# Memory_Add_Register.net
KiCad netlist of a schematic drawn in Altium Designer
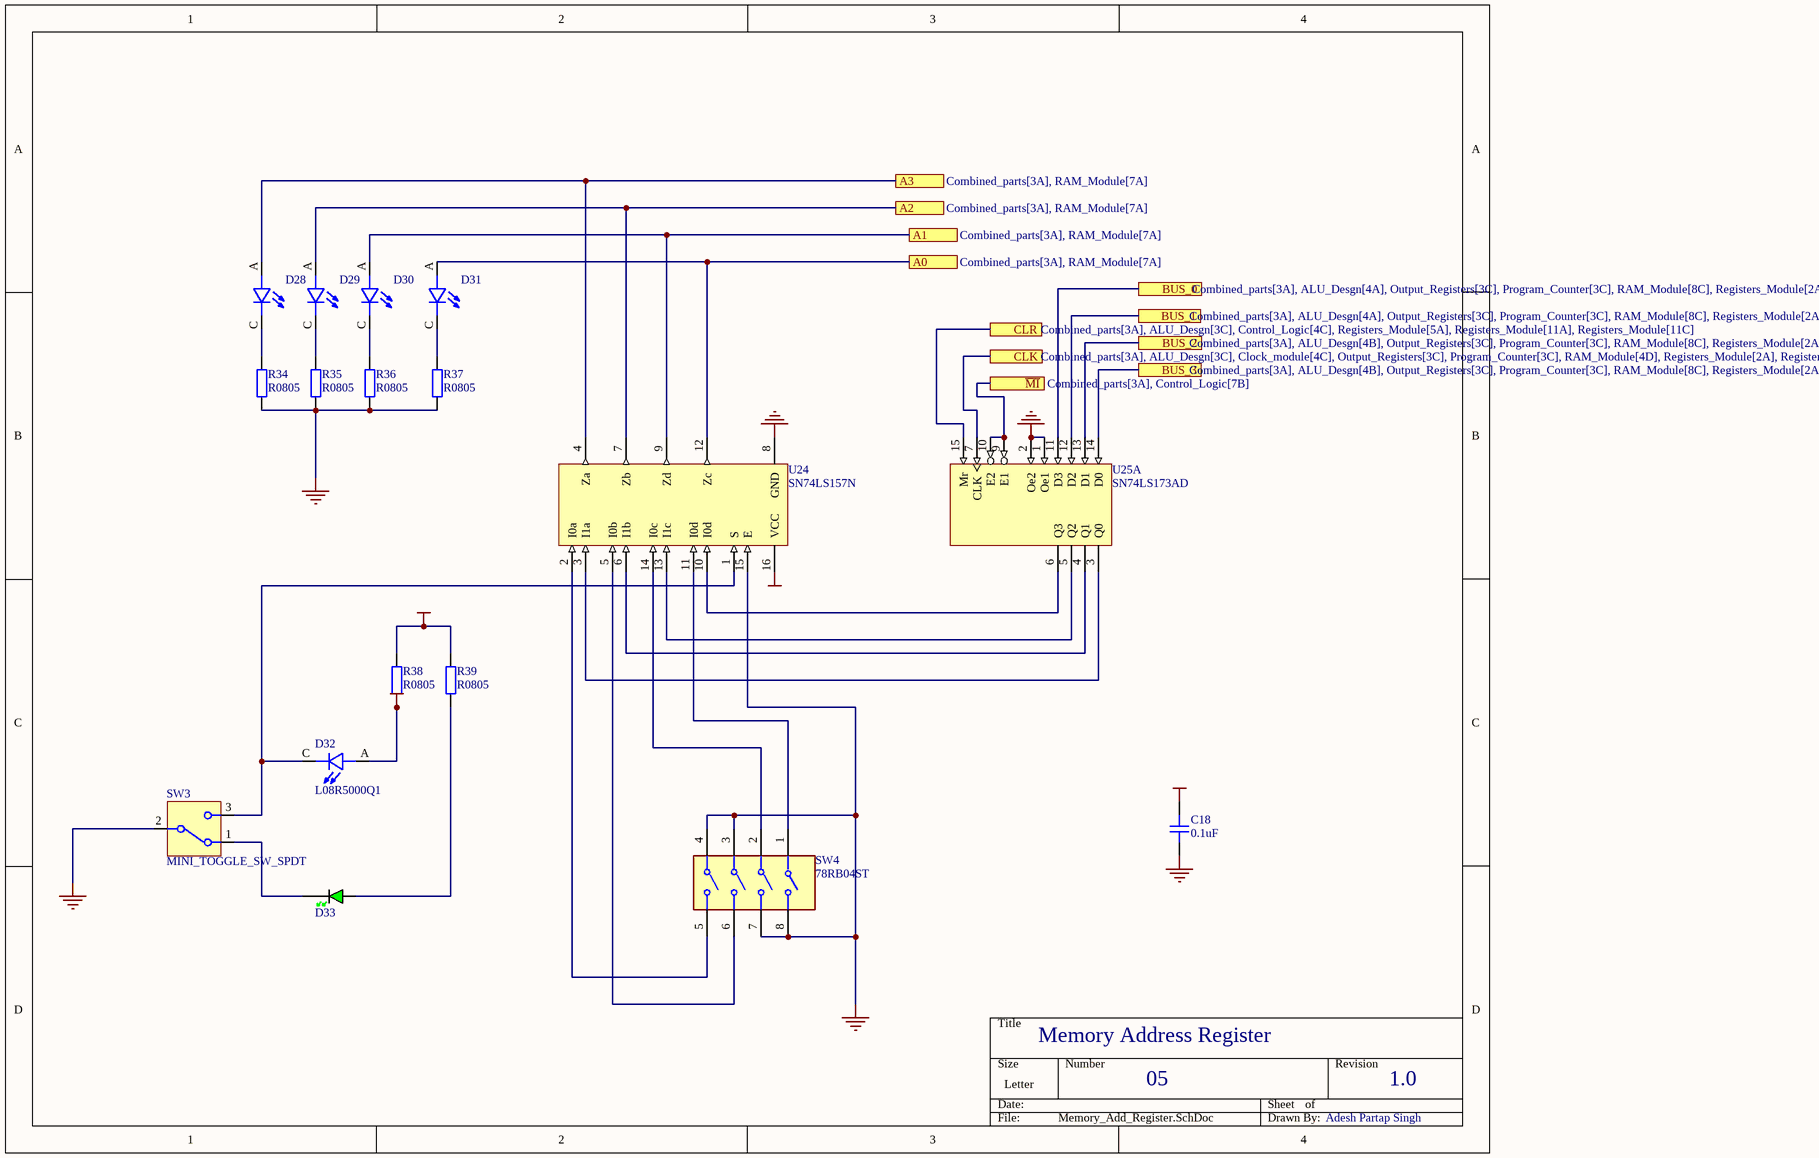
[diagram p0: Memory_Add_Register.SchDoc]

(export (version "E")
  (design (tool "Eeschema 10.0.6"))
  (components
    (comp (ref "C18")
      (value "0.1uF")
      (footprint "CAP_0805")
      (description "Capacitor SMD 0805")
      (libsource (lib "Schematic-Lib-PhilsLab") (part "CAP_0805"))
    )
    (comp (ref "D28")
      (value "L08R5000Q1")
      (footprint "LEDRD254W57D500H1070")
      (fields (field (name "MF") "LED Technology"))
      (libsource (lib "8BIT_COMP_LIB") (part "L08R5000Q1"))
    )
    (comp (ref "D29")
      (value "L08R5000Q1")
      (footprint "LEDRD254W57D500H1070")
      (fields (field (name "MF") "LED Technology"))
      (libsource (lib "8BIT_COMP_LIB") (part "L08R5000Q1"))
    )
    (comp (ref "D30")
      (value "L08R5000Q1")
      (footprint "LEDRD254W57D500H1070")
      (fields (field (name "MF") "LED Technology"))
      (libsource (lib "8BIT_COMP_LIB") (part "L08R5000Q1"))
    )
    (comp (ref "D31")
      (value "L08R5000Q1")
      (footprint "LEDRD254W57D500H1070")
      (fields (field (name "MF") "LED Technology"))
      (libsource (lib "8BIT_COMP_LIB") (part "L08R5000Q1"))
    )
    (comp (ref "D32")
      (value "L08R5000Q1")
      (footprint "LEDRD254W57D500H1070")
      (fields (field (name "MF") "LED Technology"))
      (libsource (lib "8BIT_COMP_LIB") (part "L08R5000Q1"))
    )
    (comp (ref "D33")
      (value "GREEN")
      (footprint "LED_0805_GREEN")
      (description "LED 0805 GREEN SMD")
      (libsource (lib "Schematic-Lib-PhilsLab") (part "LED_0805_GREEN"))
    )
    (comp (ref "R34")
      (value "R0805")
      (footprint "RES_0805")
      (description "Resistor SMD 0805")
      (libsource (lib "Schematic-Lib-PhilsLab") (part "RES_0805"))
    )
    (comp (ref "R35")
      (value "R0805")
      (footprint "RES_0805")
      (description "Resistor SMD 0805")
      (libsource (lib "Schematic-Lib-PhilsLab") (part "RES_0805"))
    )
    (comp (ref "R36")
      (value "R0805")
      (footprint "RES_0805")
      (description "Resistor SMD 0805")
      (libsource (lib "Schematic-Lib-PhilsLab") (part "RES_0805"))
    )
    (comp (ref "R37")
      (value "R0805")
      (footprint "RES_0805")
      (description "Resistor SMD 0805")
      (libsource (lib "Schematic-Lib-PhilsLab") (part "RES_0805"))
    )
    (comp (ref "R38")
      (value "R0805")
      (footprint "RES_0805")
      (description "Resistor SMD 0805")
      (libsource (lib "Schematic-Lib-PhilsLab") (part "RES_0805"))
    )
    (comp (ref "R39")
      (value "R0805")
      (footprint "RES_0805")
      (description "Resistor SMD 0805")
      (libsource (lib "Schematic-Lib-PhilsLab") (part "RES_0805"))
    )
    (comp (ref "SW3")
      (value "MINI_TOGGLE_SW_SPDT")
      (footprint "MINI_TOGGLE_SW_SPDT")
      (description "Mini Toggle Switch SPDT THT")
      (libsource (lib "Schematic-Lib-PhilsLab") (part "MINI_TOGGLE_SW_SPDT"))
    )
    (comp (ref "SW4")
      (value "78RB04ST")
      (footprint "FP-78RB04ST-MFG")
      (description "SWITCH SLIDE DIP SPST 150MA 30V")
      (libsource (lib "8BIT_COMP_LIB") (part "CMP-31942-000006-1"))
    )
    (comp (ref "U24")
      (value "SN74LS157N")
      (footprint "N0016A")
      (description "Quadruple 2-Line To 1-Line Data Selectors/Multiplexers, N0016A, TUBE")
      (fields
        (field (name "MANUFACTURER") "Texas Instruments")
        (field (name "GENERIC PART NUMBER") "SN74LS157")
      )
      (libsource (lib "8BIT_COMP_LIB") (part "CMP-1633-00683-2"))
    )
    (comp (ref "U25")
      (value "SN74LS173AD")
      (footprint "D0016A_N")
      (description "4-Bit D-type Registers with 3-State Outputs, D0016A, TUBE")
      (fields
        (field (name "GENERIC PART NUMBER") "SN74LS173A")
        (field (name "MANUFACTURER") "Texas Instruments")
      )
      (libsource (lib "8BIT_COMP_LIB") (part "CMP-1616-00008-3"))
    )
  )
  (nets
    (net (code "1") (name "/A0") (class "Default")
      (node (ref "D31") (pin "A") (pinfunction "A_A") (pintype "passive"))
      (node (ref "U24") (pin "12") (pinfunction "Zc_12") (pintype "output"))
    )
    (net (code "2") (name "/A1") (class "Default")
      (node (ref "D30") (pin "A") (pinfunction "A_A") (pintype "passive"))
      (node (ref "U24") (pin "9") (pinfunction "Zd_9") (pintype "output"))
    )
    (net (code "3") (name "/A2") (class "Default")
      (node (ref "D29") (pin "A") (pinfunction "A_A") (pintype "passive"))
      (node (ref "U24") (pin "7") (pinfunction "Zb_7") (pintype "output"))
    )
    (net (code "4") (name "/A3") (class "Default")
      (node (ref "D28") (pin "A") (pinfunction "A_A") (pintype "passive"))
      (node (ref "U24") (pin "4") (pinfunction "Za_4") (pintype "output"))
    )
    (net (code "5") (name "/BUS_0") (class "Default")
      (node (ref "U25") (pin "11") (pinfunction "D3_11") (pintype "input"))
    )
    (net (code "6") (name "/BUS_1") (class "Default")
      (node (ref "U25") (pin "12") (pinfunction "D2_12") (pintype "input"))
    )
    (net (code "7") (name "/BUS_2") (class "Default")
      (node (ref "U25") (pin "13") (pinfunction "D1_13") (pintype "input"))
    )
    (net (code "8") (name "/BUS_3") (class "Default")
      (node (ref "U25") (pin "14") (pinfunction "D0_14") (pintype "input"))
    )
    (net (code "9") (name "/CLK") (class "Default")
      (node (ref "U25") (pin "7") (pinfunction "CLK_7") (pintype "input"))
    )
    (net (code "10") (name "/CLR") (class "Default")
      (node (ref "U25") (pin "15") (pinfunction "Mr_15") (pintype "input"))
    )
    (net (code "11") (name "/~{MI}") (class "Default")
      (node (ref "U25") (pin "10") (pinfunction "E2_10") (pintype "input"))
      (node (ref "U25") (pin "9") (pinfunction "E1_9") (pintype "input"))
    )
    (net (code "12") (name "GND") (class "Default")
      (node (ref "C18") (pin "1") (pinfunction "1_1") (pintype "passive"))
      (node (ref "R34") (pin "1") (pinfunction "1_1") (pintype "passive"))
      (node (ref "R35") (pin "1") (pinfunction "1_1") (pintype "passive"))
      (node (ref "R36") (pin "1") (pinfunction "1_1") (pintype "passive"))
      (node (ref "R37") (pin "1") (pinfunction "1_1") (pintype "passive"))
      (node (ref "SW3") (pin "2") (pinfunction "COM_2") (pintype "passive"))
      (node (ref "SW4") (pin "3") (pinfunction "3_3") (pintype "passive"))
      (node (ref "SW4") (pin "4") (pinfunction "4_4") (pintype "passive"))
      (node (ref "SW4") (pin "7") (pinfunction "7_7") (pintype "passive"))
      (node (ref "SW4") (pin "8") (pinfunction "8_8") (pintype "passive"))
      (node (ref "U24") (pin "15") (pinfunction "E_15") (pintype "input"))
      (node (ref "U24") (pin "8") (pinfunction "GND_8") (pintype "power_in"))
      (node (ref "U25") (pin "1") (pinfunction "Oe1_1") (pintype "input"))
      (node (ref "U25") (pin "2") (pinfunction "Oe2_2") (pintype "input"))
    )
    (net (code "13") (name "Net-(D28-PadC)") (class "Default")
      (node (ref "D28") (pin "C") (pinfunction "C_C") (pintype "passive"))
      (node (ref "R34") (pin "2") (pinfunction "2_2") (pintype "passive"))
    )
    (net (code "14") (name "Net-(D29-PadC)") (class "Default")
      (node (ref "D29") (pin "C") (pinfunction "C_C") (pintype "passive"))
      (node (ref "R35") (pin "2") (pinfunction "2_2") (pintype "passive"))
    )
    (net (code "15") (name "Net-(D30-PadC)") (class "Default")
      (node (ref "D30") (pin "C") (pinfunction "C_C") (pintype "passive"))
      (node (ref "R36") (pin "2") (pinfunction "2_2") (pintype "passive"))
    )
    (net (code "16") (name "Net-(D31-PadC)") (class "Default")
      (node (ref "D31") (pin "C") (pinfunction "C_C") (pintype "passive"))
      (node (ref "R37") (pin "2") (pinfunction "2_2") (pintype "passive"))
    )
    (net (code "17") (name "Net-(D33-PadA)") (class "Default")
      (node (ref "D33") (pin "A") (pinfunction "A_A") (pintype "passive"))
      (node (ref "R39") (pin "1") (pinfunction "1_1") (pintype "passive"))
    )
    (net (code "18") (name "Net-(D33-PadK)") (class "Default")
      (node (ref "D33") (pin "K") (pinfunction "K_K") (pintype "passive"))
      (node (ref "SW3") (pin "1") (pinfunction "1_1") (pintype "passive"))
    )
    (net (code "19") (name "Net-(SW4-Pad1)") (class "Default")
      (node (ref "SW4") (pin "1") (pinfunction "1_1") (pintype "passive"))
      (node (ref "U24") (pin "11") (pinfunction "I0d_11") (pintype "input"))
    )
    (net (code "20") (name "Net-(U24-I0a)") (class "Default")
      (node (ref "SW4") (pin "5") (pinfunction "5_5") (pintype "passive"))
      (node (ref "U24") (pin "2") (pinfunction "I0a_2") (pintype "input"))
    )
    (net (code "21") (name "Net-(U24-I0b)") (class "Default")
      (node (ref "SW4") (pin "6") (pinfunction "6_6") (pintype "passive"))
      (node (ref "U24") (pin "5") (pinfunction "I0b_5") (pintype "input"))
    )
    (net (code "22") (name "Net-(U24-I0c)") (class "Default")
      (node (ref "SW4") (pin "2") (pinfunction "2_2") (pintype "passive"))
      (node (ref "U24") (pin "14") (pinfunction "I0c_14") (pintype "input"))
    )
    (net (code "23") (name "Net-(U24-I1a)") (class "Default")
      (node (ref "U24") (pin "3") (pinfunction "I1a_3") (pintype "input"))
      (node (ref "U25") (pin "3") (pinfunction "Q0_3") (pintype "tri_state"))
    )
    (net (code "24") (name "Net-(U24-I1b)") (class "Default")
      (node (ref "U24") (pin "6") (pinfunction "I1b_6") (pintype "input"))
      (node (ref "U25") (pin "4") (pinfunction "Q1_4") (pintype "tri_state"))
    )
    (net (code "25") (name "Net-(U24-I1c)") (class "Default")
      (node (ref "U24") (pin "13") (pinfunction "I1c_13") (pintype "input"))
      (node (ref "U25") (pin "5") (pinfunction "Q2_5") (pintype "tri_state"))
    )
    (net (code "26") (name "Net-(U24-S)") (class "Default")
      (node (ref "D32") (pin "C") (pinfunction "C_C") (pintype "passive"))
      (node (ref "SW3") (pin "3") (pinfunction "3_3") (pintype "passive"))
      (node (ref "U24") (pin "1") (pinfunction "S_1") (pintype "input"))
    )
    (net (code "27") (name "Net-(U25A-Q3)") (class "Default")
      (node (ref "U24") (pin "10") (pinfunction "I0d_10") (pintype "input"))
      (node (ref "U25") (pin "6") (pinfunction "Q3_6") (pintype "tri_state"))
    )
    (net (code "28") (name "VCC") (class "Default")
      (node (ref "C18") (pin "2") (pinfunction "2_2") (pintype "passive"))
      (node (ref "D32") (pin "A") (pinfunction "A_A") (pintype "passive"))
      (node (ref "R38") (pin "1") (pinfunction "1_1") (pintype "passive"))
      (node (ref "R38") (pin "2") (pinfunction "2_2") (pintype "passive"))
      (node (ref "R39") (pin "2") (pinfunction "2_2") (pintype "passive"))
      (node (ref "U24") (pin "16") (pinfunction "VCC_16") (pintype "power_in"))
    )
  )
)
